# dcdc.net
KiCad netlist of a schematic drawn in Altium Designer
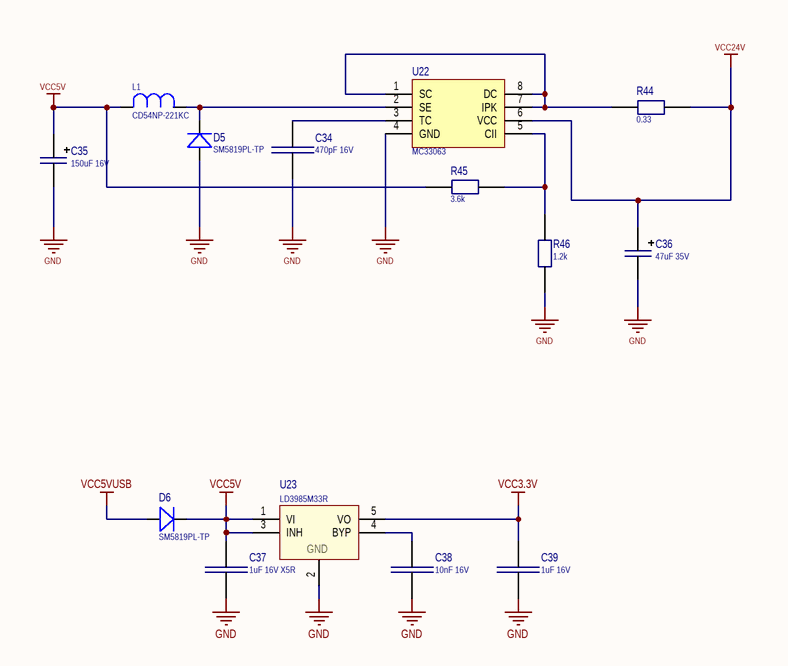
[diagram p0: dcdc.schdoc]

(export (version "E")
  (design (tool "Eeschema 10.0.6"))
  (components
    (comp (ref "C34")
      (value "470pF 16V")
      (footprint "C_0603")
      (description "Capacitor")
      (fields (field (name "PART NUMBER") "CC0603KRX7R9BB471"))
      (libsource (lib "AX_Altium_v2.3") (part "C0603"))
    )
    (comp (ref "C35")
      (value "150uF 16V")
      (footprint "TANTAL_TYPE_D")
      (description "Tantal Capacitor")
      (fields (field (name "PART NUMBER") "T491D157K016AT"))
      (libsource (lib "capacitors") (part "TANTAL_CAP"))
    )
    (comp (ref "C36")
      (value "47uF 35V")
      (footprint "TANTAL_TYPE_X")
      (description "Tantal Capacitor")
      (fields (field (name "PART NUMBER") "T491X476K035AT"))
      (libsource (lib "capacitors") (part "TANTAL_CAP"))
    )
    (comp (ref "C37")
      (value "1uF 16V X5R")
      (footprint "C_0603")
      (description "Capacitor")
      (fields (field (name "PART NUMBER") "CC0603KRX7R7BB105"))
      (libsource (lib "AX_Altium_v2.3") (part "C0603"))
    )
    (comp (ref "C38")
      (value "10nF 16V")
      (footprint "C_0603")
      (description "Capacitor")
      (fields (field (name "PART NUMBER") "CC0603JRX7R7BB103"))
      (libsource (lib "AX_Altium_v2.3") (part "C0603"))
    )
    (comp (ref "C39")
      (value "1uF 16V")
      (footprint "C_0603")
      (description "Capacitor")
      (fields (field (name "PART NUMBER") "CC0603KRX7R7BB105"))
      (libsource (lib "AX_Altium_v2.3") (part "C0603"))
    )
    (comp (ref "D5")
      (value "SM5819PL-TP")
      (footprint "SOD-123")
      (description "Diode")
      (libsource (lib "AX_Altium_v2.3") (part "D_SOD123"))
    )
    (comp (ref "D6")
      (value "SM5819PL-TP")
      (footprint "SOD-123")
      (description "Diode")
      (libsource (lib "AX_Altium_v2.3") (part "D_SOD123"))
    )
    (comp (ref "L1")
      (value "CD54NP-221KC")
      (footprint "CD54NP")
      (description "Inductor")
      (libsource (lib "AX_Altium_v2.3") (part "L_CD54NP"))
    )
    (comp (ref "R44")
      (value "0.33")
      (footprint "R_1206")
      (description "Resistor")
      (fields (field (name "PART NUMBER") "RL1206FR-070R33L"))
      (libsource (lib "resistors") (part "RES_SMD"))
    )
    (comp (ref "R45")
      (value "3.6k")
      (footprint "R_0603")
      (description "Resistor")
      (fields (field (name "PART NUMBER") "RC0603FR-073K6L"))
      (libsource (lib "resistors") (part "RES_SMD"))
    )
    (comp (ref "R46")
      (value "1.2k")
      (footprint "R_0603")
      (description "Resistor")
      (fields (field (name "PART NUMBER") "RC0603FR-071K2L"))
      (libsource (lib "resistors") (part "RES_SMD"))
    )
    (comp (ref "U22")
      (value "MC33063")
      (footprint "SO-8")
      (description "Step-up/down IC")
      (libsource (lib "dcdc_ldo_ref") (part "MC33063"))
    )
    (comp (ref "U23")
      (value "LD3985M33R")
      (footprint "SOT23-5")
      (description "LDO")
      (libsource (lib "AX_Altium_v2.3") (part "LD3985M33R"))
    )
  )
  (nets
    (net (code "1") (name "GND") (class "Default")
      (node (ref "C34") (pin "1") (pinfunction "1_1") (pintype "passive"))
      (node (ref "C35") (pin "2") (pinfunction "2_2") (pintype "passive"))
      (node (ref "C36") (pin "2") (pinfunction "2_2") (pintype "passive"))
      (node (ref "C37") (pin "1") (pinfunction "1_1") (pintype "passive"))
      (node (ref "C38") (pin "1") (pinfunction "1_1") (pintype "passive"))
      (node (ref "C39") (pin "1") (pinfunction "1_1") (pintype "passive"))
      (node (ref "D5") (pin "1") (pinfunction "A_1") (pintype "passive"))
      (node (ref "R46") (pin "1") (pinfunction "1_1") (pintype "passive"))
      (node (ref "U22") (pin "4") (pinfunction "GND_4") (pintype "passive"))
      (node (ref "U23") (pin "2") (pinfunction "GND_2") (pintype "passive"))
    )
    (net (code "2") (name "Net-(D5-K)") (class "Default")
      (node (ref "D5") (pin "2") (pinfunction "K_2") (pintype "passive"))
      (node (ref "L1") (pin "1") (pintype "passive"))
      (node (ref "U22") (pin "2") (pinfunction "SE_2") (pintype "passive"))
    )
    (net (code "3") (name "Net-(U22-CII)") (class "Default")
      (node (ref "R45") (pin "2") (pinfunction "2_2") (pintype "passive"))
      (node (ref "R46") (pin "2") (pinfunction "2_2") (pintype "passive"))
      (node (ref "U22") (pin "5") (pinfunction "CII_5") (pintype "passive"))
    )
    (net (code "4") (name "Net-(U22-DC)") (class "Default")
      (node (ref "R44") (pin "2") (pinfunction "2_2") (pintype "passive"))
      (node (ref "U22") (pin "1") (pinfunction "SC_1") (pintype "passive"))
      (node (ref "U22") (pin "7") (pinfunction "IPK_7") (pintype "passive"))
      (node (ref "U22") (pin "8") (pinfunction "DC_8") (pintype "passive"))
    )
    (net (code "5") (name "Net-(U22-TC)") (class "Default")
      (node (ref "C34") (pin "2") (pinfunction "2_2") (pintype "passive"))
      (node (ref "U22") (pin "3") (pinfunction "TC_3") (pintype "passive"))
    )
    (net (code "6") (name "Net-(U23-BYP)") (class "Default")
      (node (ref "C38") (pin "2") (pinfunction "2_2") (pintype "passive"))
      (node (ref "U23") (pin "4") (pinfunction "BYP_4") (pintype "passive"))
    )
    (net (code "7") (name "VCC3.3V") (class "Default")
      (node (ref "C39") (pin "2") (pinfunction "2_2") (pintype "passive"))
      (node (ref "U23") (pin "5") (pinfunction "VO_5") (pintype "passive"))
    )
    (net (code "8") (name "VCC5V") (class "Default")
      (node (ref "C35") (pin "1") (pinfunction "1_1") (pintype "passive"))
      (node (ref "C37") (pin "2") (pinfunction "2_2") (pintype "passive"))
      (node (ref "D6") (pin "2") (pinfunction "K_2") (pintype "passive"))
      (node (ref "L1") (pin "2") (pintype "passive"))
      (node (ref "R45") (pin "1") (pinfunction "1_1") (pintype "passive"))
      (node (ref "U23") (pin "1") (pinfunction "VI_1") (pintype "passive"))
      (node (ref "U23") (pin "3") (pinfunction "INH_3") (pintype "passive"))
    )
    (net (code "9") (name "VCC5VUSB") (class "Default")
      (node (ref "D6") (pin "1") (pinfunction "A_1") (pintype "passive"))
    )
    (net (code "10") (name "VCC24V") (class "Default")
      (node (ref "C36") (pin "1") (pinfunction "1_1") (pintype "passive"))
      (node (ref "R44") (pin "1") (pinfunction "1_1") (pintype "passive"))
      (node (ref "U22") (pin "6") (pinfunction "VCC_6") (pintype "passive"))
    )
  )
)
